# Power.net
KiCad netlist of a schematic drawn in Altium Designer
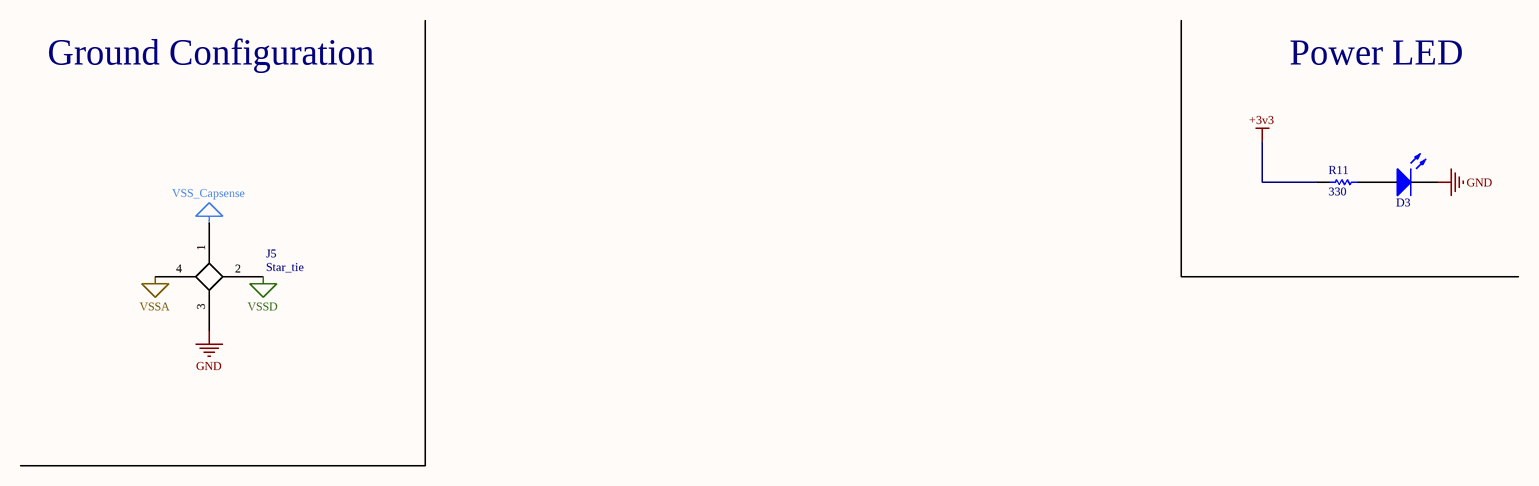
[diagram p0: Power.SchDoc]

(export (version "E")
  (design (tool "Eeschema 10.0.6"))
  (components
    (comp (ref "D3")
      (value "150060BS75000")
      (footprint "0603_A")
      (description "SMD mono-color Chip LED, WL-SMCW, Blue")
      (fields (field (name "MANUFACTURER") "Wuerth Elektronik"))
      (libsource (lib "Altium Content Vault") (part "WE-LED_K1A2-2"))
    )
    (comp (ref "J5") (value "Star_tie") (footprint "Star_tie") (libsource (lib "net_ties") (part "Star_tie")))
    (comp (ref "R11")
      (value "330")
      (footprint "RESC0603(1608)_L")
      (description "330R 0.1W 5% 0603 (1608 Metric)  SMD")
      (fields (field (name "TOLERANCE") "5 %") (field (name "POWER") "0.1 W"))
      (libsource (lib "Altium Content Vault") (part "RES"))
    )
  )
  (nets
    (net (code "1") (name "+3v3") (class "Default")
      (node (ref "R11") (pin "1") (pinfunction "1_1") (pintype "passive"))
    )
    (net (code "2") (name "GND") (class "Default")
      (node (ref "D3") (pin "1") (pinfunction "K_1") (pintype "passive"))
      (node (ref "J5") (pin "3") (pintype "passive"))
    )
    (net (code "3") (name "Net-(D3-A)") (class "Default")
      (node (ref "D3") (pin "2") (pinfunction "A_2") (pintype "passive"))
      (node (ref "R11") (pin "2") (pinfunction "2_2") (pintype "passive"))
    )
    (net (code "4") (name "VSSA") (class "Default") (node (ref "J5") (pin "4") (pintype "passive")))
    (net (code "5") (name "VSSD") (class "Default") (node (ref "J5") (pin "2") (pintype "passive")))
    (net (code "6") (name "VSS_Capsense") (class "Default") (node (ref "J5") (pin "1") (pintype "passive")))
  )
)
